# microMouse_schematic.net
KiCad netlist of a schematic drawn in EAGLE
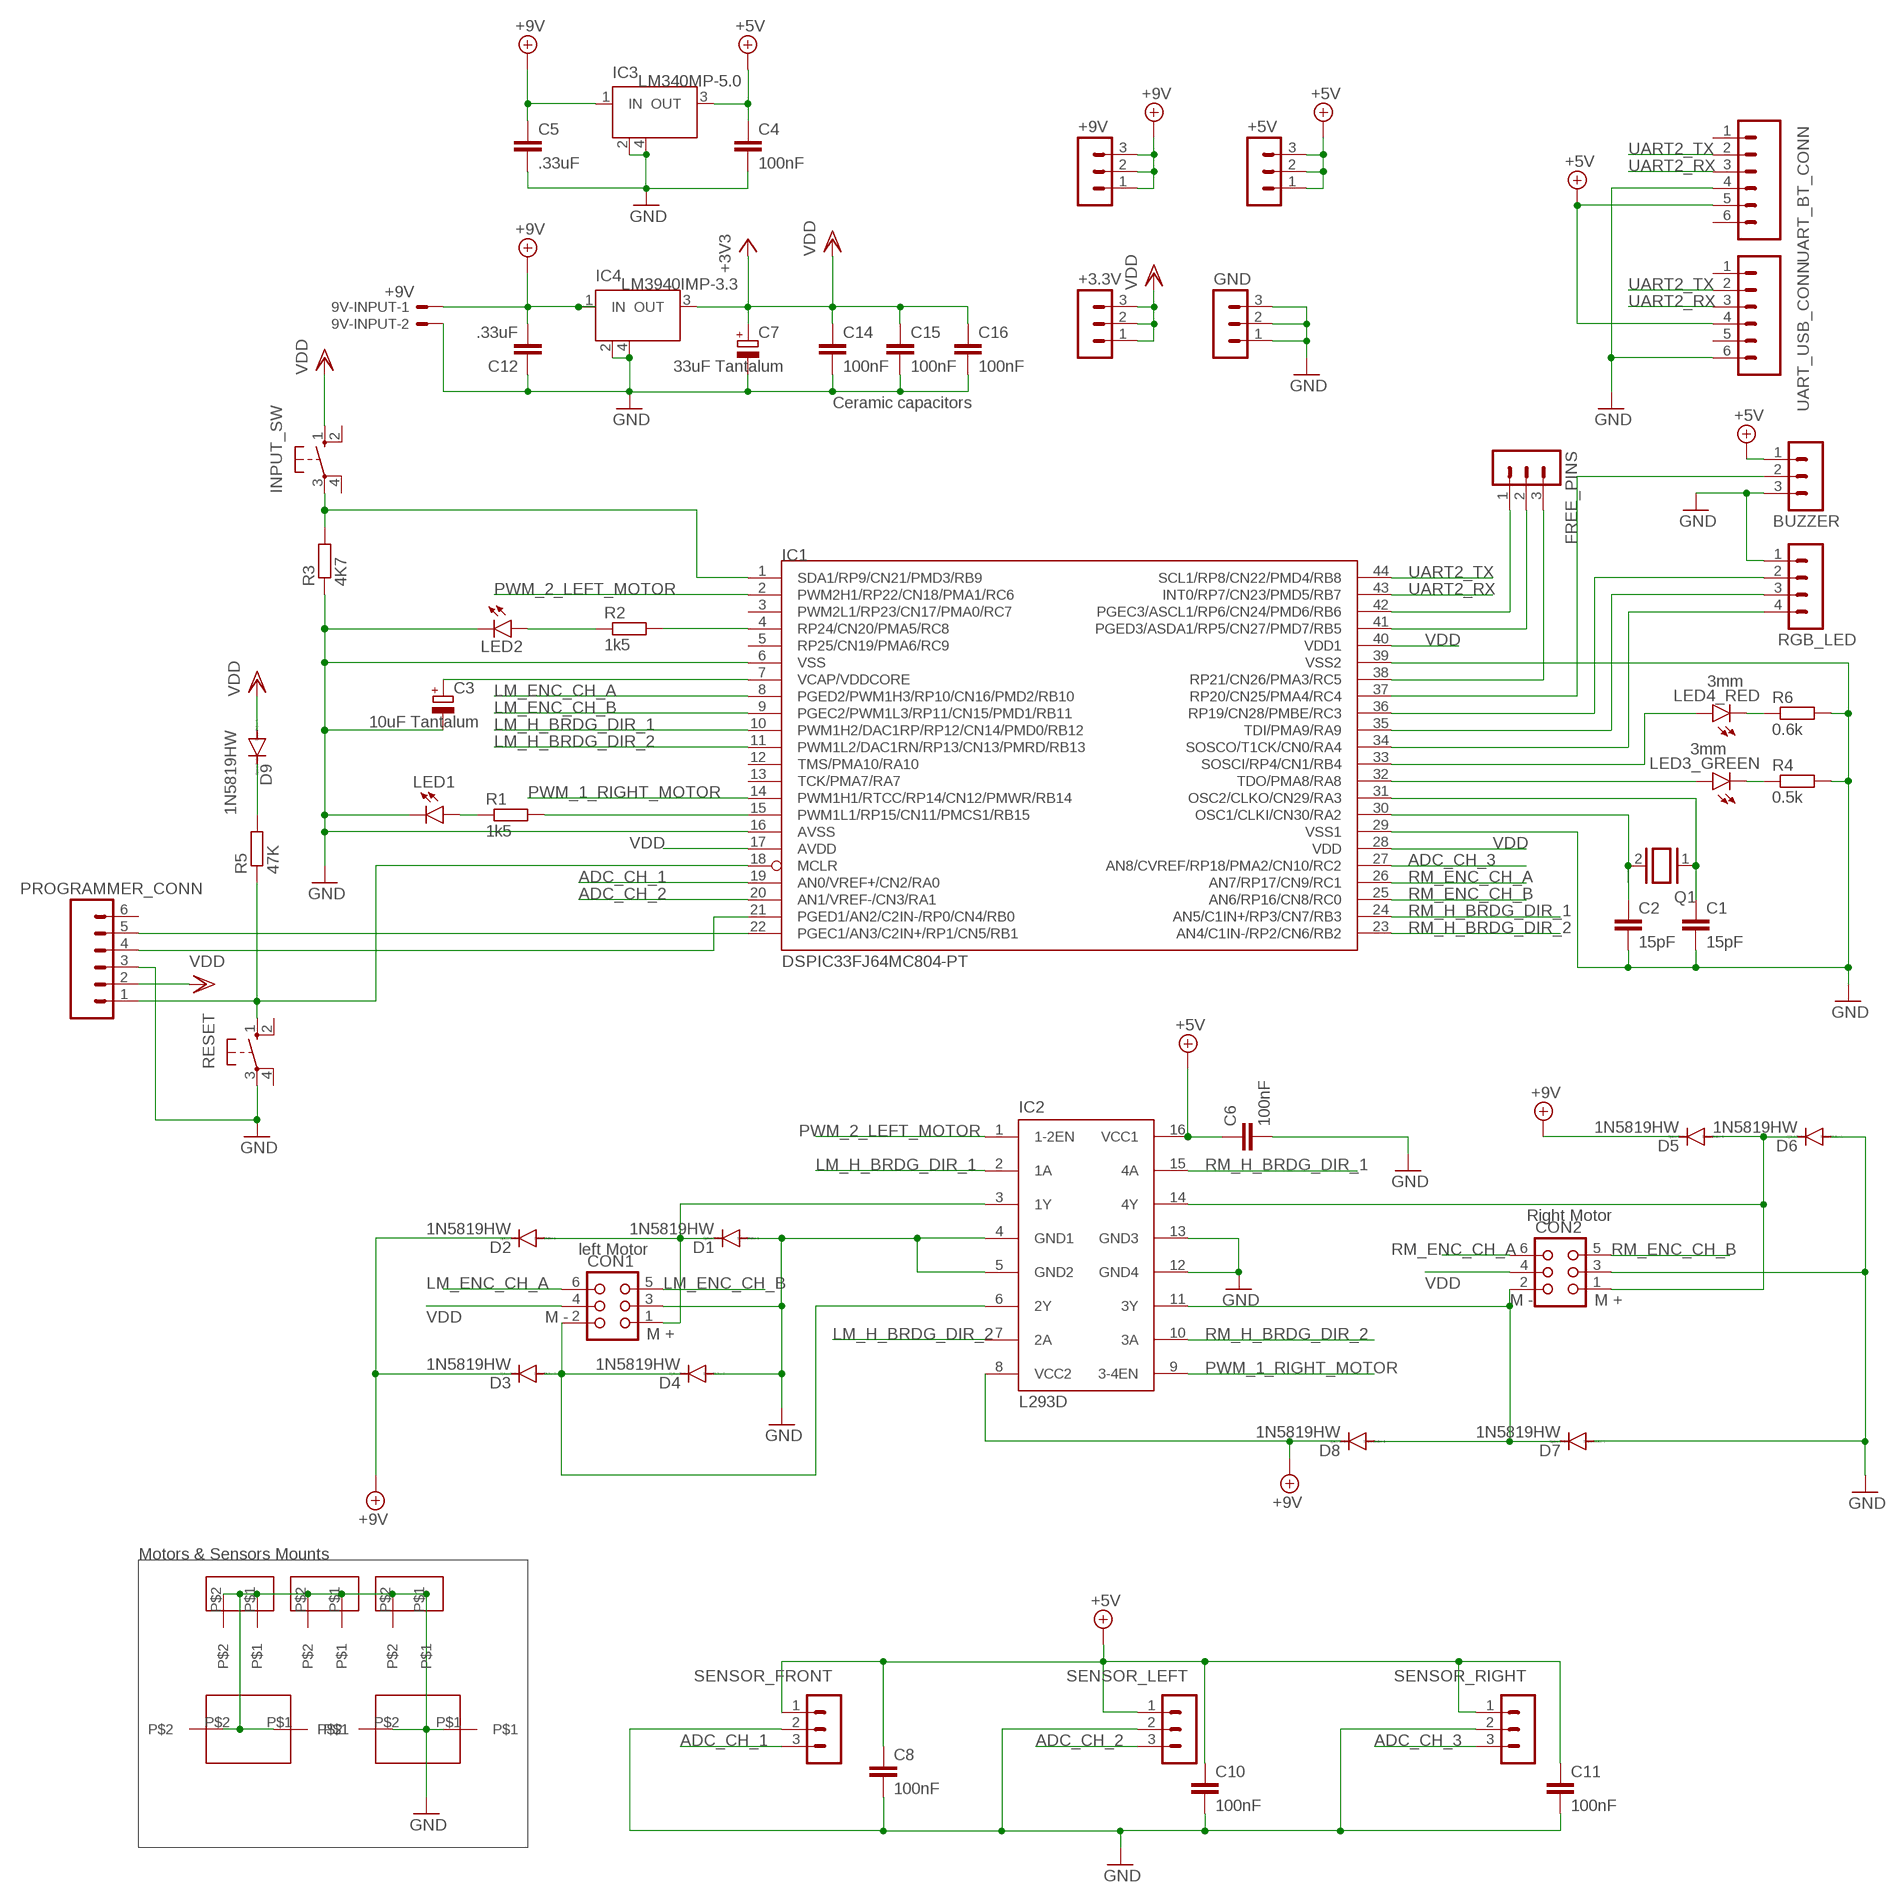
[diagram p0: schematic, sheet 1]

(export (version "E")
  (design (tool "Eeschema 10.0.6"))
  (components
    (comp (ref "+3.3V")
      (value "MA03-1")
      (footprint "eagle-import:MA03-1")
      (libsource (lib "eagle-import") (part "MA03-1"))
    )
    (comp (ref "+5V")
      (value "MA03-1")
      (footprint "eagle-import:MA03-1")
      (libsource (lib "eagle-import") (part "MA03-1"))
    )
    (comp (ref "+9V")
      (value "MA03-1")
      (footprint "eagle-import:MA03-1")
      (libsource (lib "eagle-import") (part "MA03-1"))
    )
    (comp (ref "9V-INPUT")
      (value "+9V")
      (footprint "eagle-import:22-23-2021")
      (fields (field (name "MF") "MOLEX") (field (name "MPN") "22-23-2021"))
      (libsource (lib "eagle-import") (part "22-23-2021"))
    )
    (comp (ref "BUZZER")
      (value "MA03-1")
      (footprint "eagle-import:MA03-1")
      (libsource (lib "eagle-import") (part "MA03-1"))
    )
    (comp (ref "C1")
      (value "15pF")
      (footprint "eagle-import:C0805")
      (libsource (lib "eagle-import") (part "C-EUC0805"))
    )
    (comp (ref "C2")
      (value "15pF")
      (footprint "eagle-import:C0805")
      (libsource (lib "eagle-import") (part "C-EUC0805"))
    )
    (comp (ref "C3")
      (value "10uF Tantalum")
      (footprint "eagle-import:CT3216")
      (libsource (lib "eagle-import") (part "CPOL-EUCT3216"))
    )
    (comp (ref "C4")
      (value "100nF")
      (footprint "eagle-import:C0805")
      (libsource (lib "eagle-import") (part "C-EUC0805"))
    )
    (comp (ref "C5")
      (value ".33uF")
      (footprint "eagle-import:C0805")
      (libsource (lib "eagle-import") (part "C-EUC0805"))
    )
    (comp (ref "C6")
      (value "100nF")
      (footprint "eagle-import:C0805")
      (libsource (lib "eagle-import") (part "C-EUC0805"))
    )
    (comp (ref "C7")
      (value "33uF Tantalum")
      (footprint "eagle-import:CT7343")
      (libsource (lib "eagle-import") (part "CPOL-EUCT7343"))
    )
    (comp (ref "C8")
      (value "100nF")
      (footprint "eagle-import:C0805")
      (libsource (lib "eagle-import") (part "C-EUC0805"))
    )
    (comp (ref "C10")
      (value "100nF")
      (footprint "eagle-import:C0805")
      (libsource (lib "eagle-import") (part "C-EUC0805"))
    )
    (comp (ref "C11")
      (value "100nF")
      (footprint "eagle-import:C0805")
      (libsource (lib "eagle-import") (part "C-EUC0805"))
    )
    (comp (ref "C12")
      (value ".33uF")
      (footprint "eagle-import:C0805")
      (libsource (lib "eagle-import") (part "C-EUC0805"))
    )
    (comp (ref "C14")
      (value "100nF")
      (footprint "eagle-import:C0805")
      (libsource (lib "eagle-import") (part "C-EUC0805"))
    )
    (comp (ref "C15")
      (value "100nF")
      (footprint "eagle-import:C0805")
      (libsource (lib "eagle-import") (part "C-EUC0805"))
    )
    (comp (ref "C16")
      (value "100nF")
      (footprint "eagle-import:C0805")
      (libsource (lib "eagle-import") (part "C-EUC0805"))
    )
    (comp (ref "CON1")
      (value "CON06L")
      (footprint "eagle-import:CON06L")
      (libsource (lib "eagle-import") (part "CON06L"))
    )
    (comp (ref "CON2")
      (value "CON06L")
      (footprint "eagle-import:CON06L")
      (libsource (lib "eagle-import") (part "CON06L"))
    )
    (comp (ref "D1")
      (value "1N5819HW")
      (footprint "eagle-import:SOD-123_MINI-SMA")
      (libsource (lib "eagle-import") (part "CGRM400-G1"))
    )
    (comp (ref "D2")
      (value "1N5819HW")
      (footprint "eagle-import:SOD-123_MINI-SMA")
      (libsource (lib "eagle-import") (part "CGRM400-G1"))
    )
    (comp (ref "D3")
      (value "1N5819HW")
      (footprint "eagle-import:SOD-123_MINI-SMA")
      (libsource (lib "eagle-import") (part "CGRM400-G1"))
    )
    (comp (ref "D4")
      (value "1N5819HW")
      (footprint "eagle-import:SOD-123_MINI-SMA")
      (libsource (lib "eagle-import") (part "CGRM400-G1"))
    )
    (comp (ref "D5")
      (value "1N5819HW")
      (footprint "eagle-import:SOD-123_MINI-SMA")
      (libsource (lib "eagle-import") (part "CGRM400-G1"))
    )
    (comp (ref "D6")
      (value "1N5819HW")
      (footprint "eagle-import:SOD-123_MINI-SMA")
      (libsource (lib "eagle-import") (part "CGRM400-G1"))
    )
    (comp (ref "D7")
      (value "1N5819HW")
      (footprint "eagle-import:SOD-123_MINI-SMA")
      (libsource (lib "eagle-import") (part "CGRM400-G1"))
    )
    (comp (ref "D8")
      (value "1N5819HW")
      (footprint "eagle-import:SOD-123_MINI-SMA")
      (libsource (lib "eagle-import") (part "CGRM400-G1"))
    )
    (comp (ref "D9")
      (value "1N5819HW")
      (footprint "eagle-import:SOD-123_MINI-SMA")
      (libsource (lib "eagle-import") (part "CGRM400-G1"))
    )
    (comp (ref "FREE_PINS")
      (value "MA03-1")
      (footprint "eagle-import:MA03-1")
      (libsource (lib "eagle-import") (part "MA03-1"))
    )
    (comp (ref "GND")
      (value "MA03-1")
      (footprint "eagle-import:MA03-1")
      (libsource (lib "eagle-import") (part "MA03-1"))
    )
    (comp (ref "IC1")
      (value "DSPIC33FJ64MC804-PT")
      (footprint "eagle-import:TQFP44")
      (libsource (lib "eagle-import") (part "DSPIC33FJ64MC804-PT"))
    )
    (comp (ref "IC2")
      (value "L293D")
      (footprint "eagle-import:DIL16")
      (libsource (lib "eagle-import") (part "L293D"))
    )
    (comp (ref "IC3")
      (value "LM340MP-5.0")
      (footprint "eagle-import:SOT223")
      (libsource (lib "eagle-import") (part "LM340S"))
    )
    (comp (ref "IC4")
      (value "LM3940IMP-3.3")
      (footprint "eagle-import:SOT223")
      (libsource (lib "eagle-import") (part "LM340S"))
    )
    (comp (ref "INPUT_SW")
      (value "10-XX")
      (footprint "eagle-import:B3F-10XX")
      (fields (field (name "MPN") "B3F-1000"))
      (libsource (lib "eagle-import") (part "10-XX"))
    )
    (comp (ref "LED1")
      (value "LED5MM")
      (footprint "eagle-import:LED5MM")
      (libsource (lib "eagle-import") (part "LED5MM"))
    )
    (comp (ref "LED2")
      (value "LED5MM")
      (footprint "eagle-import:LED5MM")
      (libsource (lib "eagle-import") (part "LED5MM"))
    )
    (comp (ref "LED3_GREEN")
      (value "3mm")
      (footprint "eagle-import:Q62902-B155")
      (libsource (lib "eagle-import") (part "LEDB155"))
    )
    (comp (ref "LED4_RED")
      (value "3mm")
      (footprint "eagle-import:Q62902-B155")
      (libsource (lib "eagle-import") (part "LEDB155"))
    )
    (comp (ref "PROGRAMMER_CONN")
      (value "M06")
      (footprint "eagle-import:06P")
      (libsource (lib "eagle-import") (part "M06"))
    )
    (comp (ref "Q1")
      (value "XTAL/S")
      (footprint "eagle-import:QS")
      (libsource (lib "eagle-import") (part "XTAL/S"))
    )
    (comp (ref "R1")
      (value "1k5")
      (footprint "eagle-import:R0805")
      (libsource (lib "eagle-import") (part "R-EU_R0805"))
    )
    (comp (ref "R2")
      (value "1k5")
      (footprint "eagle-import:R0805")
      (libsource (lib "eagle-import") (part "R-EU_R0805"))
    )
    (comp (ref "R3")
      (value "4K7")
      (footprint "eagle-import:R0805")
      (libsource (lib "eagle-import") (part "R-EU_R0805"))
    )
    (comp (ref "R4")
      (value "0.5k")
      (footprint "eagle-import:R0805")
      (libsource (lib "eagle-import") (part "R-EU_R0805"))
    )
    (comp (ref "R5")
      (value "47K")
      (footprint "eagle-import:R0805")
      (libsource (lib "eagle-import") (part "R-EU_R0805"))
    )
    (comp (ref "R6")
      (value "0.6k")
      (footprint "eagle-import:R0805")
      (libsource (lib "eagle-import") (part "R-EU_R0805"))
    )
    (comp (ref "RESET")
      (value "10-XX")
      (footprint "eagle-import:B3F-10XX")
      (fields (field (name "MPN") "B3F-1000"))
      (libsource (lib "eagle-import") (part "10-XX"))
    )
    (comp (ref "RGB_LED")
      (value "MA04-1")
      (footprint "eagle-import:MA04-1")
      (libsource (lib "eagle-import") (part "MA04-1"))
    )
    (comp (ref "SENSOR_FRONT")
      (value "MA03-1")
      (footprint "eagle-import:MA03-1")
      (libsource (lib "eagle-import") (part "MA03-1"))
    )
    (comp (ref "SENSOR_LEFT")
      (value "MA03-1")
      (footprint "eagle-import:MA03-1")
      (libsource (lib "eagle-import") (part "MA03-1"))
    )
    (comp (ref "SENSOR_RIGHT")
      (value "MA03-1")
      (footprint "eagle-import:MA03-1")
      (libsource (lib "eagle-import") (part "MA03-1"))
    )
    (comp (ref "SENS_MNT_F")
      (value "SENSOR_MOUNT_F")
      (footprint "eagle-import:SENSOR_MOUNT")
      (libsource (lib "eagle-import") (part "SENSOR_MOUNT"))
    )
    (comp (ref "SENS_MNT_L")
      (value "SENSOR_MOUNT_L")
      (footprint "eagle-import:SENSOR_MOUNT")
      (libsource (lib "eagle-import") (part "SENSOR_MOUNT"))
    )
    (comp (ref "SENS_MNT_R")
      (value "SENSOR_MOUNT_R")
      (footprint "eagle-import:SENSOR_MOUNT")
      (libsource (lib "eagle-import") (part "SENSOR_MOUNT"))
    )
    (comp (ref "U$1")
      (value "MOTOR_MOUNT")
      (footprint "eagle-import:MOTOR_MOUNT")
      (libsource (lib "eagle-import") (part "MOTOR_MOUNT"))
    )
    (comp (ref "U$2")
      (value "MOTOR_MOUNT")
      (footprint "eagle-import:MOTOR_MOUNT")
      (libsource (lib "eagle-import") (part "MOTOR_MOUNT"))
    )
    (comp (ref "UART_BT_CONN")
      (value "M06")
      (footprint "eagle-import:06P")
      (libsource (lib "eagle-import") (part "M06"))
    )
    (comp (ref "UART_USB_CONN")
      (value "M06")
      (footprint "eagle-import:06P")
      (libsource (lib "eagle-import") (part "M06"))
    )
  )
  (nets
    (net (code "1") (name "+3V3") (class "Default")
      (node (ref "+3.3V") (pin "1") (pinfunction "1_1") (pintype "passive"))
      (node (ref "+3.3V") (pin "2") (pinfunction "2_2") (pintype "passive"))
      (node (ref "+3.3V") (pin "3") (pinfunction "3_3") (pintype "passive"))
      (node (ref "C14") (pin "1") (pinfunction "1_1") (pintype "passive"))
      (node (ref "C15") (pin "1") (pinfunction "1_1") (pintype "passive"))
      (node (ref "C16") (pin "1") (pinfunction "1_1") (pintype "passive"))
      (node (ref "C7") (pin "+") (pinfunction "+_+") (pintype "passive"))
      (node (ref "CON1") (pin "4") (pinfunction "4_4") (pintype "passive"))
      (node (ref "CON2") (pin "4") (pinfunction "4_4") (pintype "passive"))
      (node (ref "D9") (pin "A") (pinfunction "A_A") (pintype "passive"))
      (node (ref "IC1") (pin "17") (pinfunction "AVDD_17") (pintype "power_in"))
      (node (ref "IC1") (pin "28") (pinfunction "VDD_28") (pintype "power_in"))
      (node (ref "IC1") (pin "40") (pinfunction "VDD1_40") (pintype "power_in"))
      (node (ref "IC4") (pin "3") (pinfunction "OUT_3") (pintype "passive"))
      (node (ref "INPUT_SW") (pin "1") (pinfunction "S_1") (pintype "passive"))
      (node (ref "PROGRAMMER_CONN") (pin "2") (pinfunction "2_2") (pintype "passive"))
    )
    (net (code "2") (name "+5V") (class "Default")
      (node (ref "+5V") (pin "1") (pinfunction "1_1") (pintype "passive"))
      (node (ref "+5V") (pin "2") (pinfunction "2_2") (pintype "passive"))
      (node (ref "+5V") (pin "3") (pinfunction "3_3") (pintype "passive"))
      (node (ref "BUZZER") (pin "1") (pinfunction "1_1") (pintype "passive"))
      (node (ref "C10") (pin "1") (pinfunction "1_1") (pintype "passive"))
      (node (ref "C11") (pin "1") (pinfunction "1_1") (pintype "passive"))
      (node (ref "C4") (pin "1") (pinfunction "1_1") (pintype "passive"))
      (node (ref "C6") (pin "1") (pinfunction "1_1") (pintype "passive"))
      (node (ref "C8") (pin "1") (pinfunction "1_1") (pintype "passive"))
      (node (ref "IC2") (pin "16") (pinfunction "VCC1_16") (pintype "power_in"))
      (node (ref "IC3") (pin "3") (pinfunction "OUT_3") (pintype "passive"))
      (node (ref "SENSOR_FRONT") (pin "1") (pinfunction "1_1") (pintype "passive"))
      (node (ref "SENSOR_LEFT") (pin "1") (pinfunction "1_1") (pintype "passive"))
      (node (ref "SENSOR_RIGHT") (pin "1") (pinfunction "1_1") (pintype "passive"))
      (node (ref "UART_BT_CONN") (pin "5") (pinfunction "5_5") (pintype "passive"))
      (node (ref "UART_USB_CONN") (pin "4") (pinfunction "4_4") (pintype "passive"))
    )
    (net (code "3") (name "+9V") (class "Default")
      (node (ref "+9V") (pin "1") (pinfunction "1_1") (pintype "passive"))
      (node (ref "+9V") (pin "2") (pinfunction "2_2") (pintype "passive"))
      (node (ref "+9V") (pin "3") (pinfunction "3_3") (pintype "passive"))
      (node (ref "9V-INPUT") (pin "1") (pinfunction "S_1") (pintype "passive"))
      (node (ref "C12") (pin "2") (pinfunction "2_2") (pintype "passive"))
      (node (ref "C5") (pin "1") (pinfunction "1_1") (pintype "passive"))
      (node (ref "D2") (pin "C") (pinfunction "C_C") (pintype "passive"))
      (node (ref "D3") (pin "C") (pinfunction "C_C") (pintype "passive"))
      (node (ref "D5") (pin "C") (pinfunction "C_C") (pintype "passive"))
      (node (ref "D8") (pin "C") (pinfunction "C_C") (pintype "passive"))
      (node (ref "IC2") (pin "8") (pinfunction "VCC2_8") (pintype "power_in"))
      (node (ref "IC3") (pin "1") (pinfunction "IN_1") (pintype "input"))
      (node (ref "IC4") (pin "1") (pinfunction "IN_1") (pintype "input"))
    )
    (net (code "4") (name "/ADC_CH_1") (class "Default")
      (node (ref "IC1") (pin "19") (pinfunction "AN0/VREF+/CN2/RA0_19") (pintype "bidirectional"))
      (node (ref "SENSOR_FRONT") (pin "3") (pinfunction "3_3") (pintype "passive"))
    )
    (net (code "5") (name "/ADC_CH_2") (class "Default")
      (node (ref "IC1") (pin "20") (pinfunction "AN1/VREF-/CN3/RA1_20") (pintype "bidirectional"))
      (node (ref "SENSOR_LEFT") (pin "3") (pinfunction "3_3") (pintype "passive"))
    )
    (net (code "6") (name "/ADC_CH_3") (class "Default")
      (node (ref "IC1") (pin "27") (pinfunction "AN8/CVREF/RP18/PMA2/CN10/RC2_27") (pintype "bidirectional"))
      (node (ref "SENSOR_RIGHT") (pin "3") (pinfunction "3_3") (pintype "passive"))
    )
    (net (code "7") (name "/LM_ENC_CH_A") (class "Default")
      (node (ref "CON1") (pin "6") (pinfunction "6_6") (pintype "passive"))
      (node (ref "IC1") (pin "8") (pinfunction "PGED2/PWM1H3/RP10/CN16/PMD2/RB10_8") (pintype "bidirectional"))
    )
    (net (code "8") (name "/LM_ENC_CH_B") (class "Default")
      (node (ref "CON1") (pin "5") (pinfunction "5_5") (pintype "passive"))
      (node (ref "IC1") (pin "9") (pinfunction "PGEC2/PWM1L3/RP11/CN15/PMD1/RB11_9") (pintype "bidirectional"))
    )
    (net (code "9") (name "/LM_H_BRDG_DIR_1") (class "Default")
      (node (ref "IC1") (pin "10") (pinfunction "PWM1H2/DAC1RP/RP12/CN14/PMD0/RB12_10") (pintype "bidirectional"))
      (node (ref "IC2") (pin "2") (pinfunction "1A_2") (pintype "input"))
    )
    (net (code "10") (name "/LM_H_BRDG_DIR_2") (class "Default")
      (node (ref "IC1") (pin "11") (pinfunction "PWM1L2/DAC1RN/RP13/CN13/PMRD/RB13_11") (pintype "bidirectional"))
      (node (ref "IC2") (pin "7") (pinfunction "2A_7") (pintype "input"))
    )
    (net (code "11") (name "/PWM_1_RIGHT_MOTOR") (class "Default")
      (node (ref "IC1") (pin "14") (pinfunction "PWM1H1/RTCC/RP14/CN12/PMWR/RB14_14") (pintype "bidirectional"))
      (node (ref "IC2") (pin "9") (pinfunction "3-4EN_9") (pintype "input"))
    )
    (net (code "12") (name "/PWM_2_LEFT_MOTOR") (class "Default")
      (node (ref "IC1") (pin "2") (pinfunction "PWM2H1/RP22/CN18/PMA1/RC6_2") (pintype "bidirectional"))
      (node (ref "IC2") (pin "1") (pinfunction "1-2EN_1") (pintype "input"))
    )
    (net (code "13") (name "/RM_ENC_CH_A") (class "Default")
      (node (ref "CON2") (pin "6") (pinfunction "6_6") (pintype "passive"))
      (node (ref "IC1") (pin "26") (pinfunction "AN7/RP17/CN9/RC1_26") (pintype "bidirectional"))
    )
    (net (code "14") (name "/RM_ENC_CH_B") (class "Default")
      (node (ref "CON2") (pin "5") (pinfunction "5_5") (pintype "passive"))
      (node (ref "IC1") (pin "25") (pinfunction "AN6/RP16/CN8/RC0_25") (pintype "bidirectional"))
    )
    (net (code "15") (name "/RM_H_BRDG_DIR_1") (class "Default")
      (node (ref "IC1") (pin "24") (pinfunction "AN5/C1IN+/RP3/CN7/RB3_24") (pintype "bidirectional"))
      (node (ref "IC2") (pin "15") (pinfunction "4A_15") (pintype "input"))
    )
    (net (code "16") (name "/RM_H_BRDG_DIR_2") (class "Default")
      (node (ref "IC1") (pin "23") (pinfunction "AN4/C1IN-/RP2/CN6/RB2_23") (pintype "bidirectional"))
      (node (ref "IC2") (pin "10") (pinfunction "3A_10") (pintype "input"))
    )
    (net (code "17") (name "/UART2_RX") (class "Default")
      (node (ref "IC1") (pin "43") (pinfunction "INT0/RP7/CN23/PMD5/RB7_43") (pintype "bidirectional"))
      (node (ref "UART_BT_CONN") (pin "3") (pinfunction "3_3") (pintype "passive"))
      (node (ref "UART_USB_CONN") (pin "3") (pinfunction "3_3") (pintype "passive"))
    )
    (net (code "18") (name "/UART2_TX") (class "Default")
      (node (ref "IC1") (pin "44") (pinfunction "SCL1/RP8/CN22/PMD4/RB8_44") (pintype "bidirectional"))
      (node (ref "UART_BT_CONN") (pin "2") (pinfunction "2_2") (pintype "passive"))
      (node (ref "UART_USB_CONN") (pin "2") (pinfunction "2_2") (pintype "passive"))
    )
    (net (code "19") (name "GND") (class "Default")
      (node (ref "9V-INPUT") (pin "2") (pinfunction "S_2") (pintype "passive"))
      (node (ref "BUZZER") (pin "3") (pinfunction "3_3") (pintype "passive"))
      (node (ref "C1") (pin "2") (pinfunction "2_2") (pintype "passive"))
      (node (ref "C10") (pin "2") (pinfunction "2_2") (pintype "passive"))
      (node (ref "C11") (pin "2") (pinfunction "2_2") (pintype "passive"))
      (node (ref "C12") (pin "1") (pinfunction "1_1") (pintype "passive"))
      (node (ref "C14") (pin "2") (pinfunction "2_2") (pintype "passive"))
      (node (ref "C15") (pin "2") (pinfunction "2_2") (pintype "passive"))
      (node (ref "C16") (pin "2") (pinfunction "2_2") (pintype "passive"))
      (node (ref "C2") (pin "2") (pinfunction "2_2") (pintype "passive"))
      (node (ref "C3") (pin "-") (pinfunction "-_-") (pintype "passive"))
      (node (ref "C4") (pin "2") (pinfunction "2_2") (pintype "passive"))
      (node (ref "C5") (pin "2") (pinfunction "2_2") (pintype "passive"))
      (node (ref "C6") (pin "2") (pinfunction "2_2") (pintype "passive"))
      (node (ref "C7") (pin "-") (pinfunction "-_-") (pintype "passive"))
      (node (ref "C8") (pin "2") (pinfunction "2_2") (pintype "passive"))
      (node (ref "CON1") (pin "3") (pinfunction "3_3") (pintype "passive"))
      (node (ref "CON2") (pin "3") (pinfunction "3_3") (pintype "passive"))
      (node (ref "D1") (pin "A") (pinfunction "A_A") (pintype "passive"))
      (node (ref "D4") (pin "A") (pinfunction "A_A") (pintype "passive"))
      (node (ref "D6") (pin "A") (pinfunction "A_A") (pintype "passive"))
      (node (ref "D7") (pin "A") (pinfunction "A_A") (pintype "passive"))
      (node (ref "GND") (pin "1") (pinfunction "1_1") (pintype "passive"))
      (node (ref "GND") (pin "2") (pinfunction "2_2") (pintype "passive"))
      (node (ref "GND") (pin "3") (pinfunction "3_3") (pintype "passive"))
      (node (ref "IC1") (pin "16") (pinfunction "AVSS_16") (pintype "power_in"))
      (node (ref "IC1") (pin "29") (pinfunction "VSS1_29") (pintype "power_in"))
      (node (ref "IC1") (pin "39") (pinfunction "VSS2_39") (pintype "power_in"))
      (node (ref "IC1") (pin "6") (pinfunction "VSS_6") (pintype "power_in"))
      (node (ref "IC2") (pin "12") (pinfunction "GND4_12") (pintype "power_in"))
      (node (ref "IC2") (pin "13") (pinfunction "GND3_13") (pintype "power_in"))
      (node (ref "IC2") (pin "4") (pinfunction "GND1_4") (pintype "power_in"))
      (node (ref "IC2") (pin "5") (pinfunction "GND2_5") (pintype "power_in"))
      (node (ref "IC3") (pin "2") (pinfunction "GND_2") (pintype "power_in"))
      (node (ref "IC3") (pin "4") (pinfunction "GND_4") (pintype "power_in"))
      (node (ref "IC4") (pin "2") (pinfunction "GND_2") (pintype "power_in"))
      (node (ref "IC4") (pin "4") (pinfunction "GND_4") (pintype "power_in"))
      (node (ref "LED1") (pin "K") (pinfunction "C_K") (pintype "passive"))
      (node (ref "LED2") (pin "K") (pinfunction "C_K") (pintype "passive"))
      (node (ref "PROGRAMMER_CONN") (pin "3") (pinfunction "3_3") (pintype "passive"))
      (node (ref "R3") (pin "1") (pinfunction "1_1") (pintype "passive"))
      (node (ref "R4") (pin "2") (pinfunction "2_2") (pintype "passive"))
      (node (ref "R6") (pin "2") (pinfunction "2_2") (pintype "passive"))
      (node (ref "RESET") (pin "3") (pinfunction "P_3") (pintype "passive"))
      (node (ref "RGB_LED") (pin "1") (pinfunction "1_1") (pintype "passive"))
      (node (ref "SENSOR_FRONT") (pin "2") (pinfunction "2_2") (pintype "passive"))
      (node (ref "SENSOR_LEFT") (pin "2") (pinfunction "2_2") (pintype "passive"))
      (node (ref "SENSOR_RIGHT") (pin "2") (pinfunction "2_2") (pintype "passive"))
      (node (ref "SENS_MNT_F") (pin "P$1") (pinfunction "P$1_P$1") (pintype "bidirectional"))
      (node (ref "SENS_MNT_F") (pin "P$2") (pinfunction "P$2_P$2") (pintype "bidirectional"))
      (node (ref "SENS_MNT_L") (pin "P$1") (pinfunction "P$1_P$1") (pintype "bidirectional"))
      (node (ref "SENS_MNT_L") (pin "P$2") (pinfunction "P$2_P$2") (pintype "bidirectional"))
      (node (ref "SENS_MNT_R") (pin "P$1") (pinfunction "P$1_P$1") (pintype "bidirectional"))
      (node (ref "SENS_MNT_R") (pin "P$2") (pinfunction "P$2_P$2") (pintype "bidirectional"))
      (node (ref "U$1") (pin "P$1") (pinfunction "P$1_P$1") (pintype "bidirectional"))
      (node (ref "U$1") (pin "P$2") (pinfunction "P$2_P$2") (pintype "bidirectional"))
      (node (ref "U$2") (pin "P$1") (pinfunction "P$1_P$1") (pintype "bidirectional"))
      (node (ref "U$2") (pin "P$2") (pinfunction "P$2_P$2") (pintype "bidirectional"))
      (node (ref "UART_BT_CONN") (pin "4") (pinfunction "4_4") (pintype "passive"))
      (node (ref "UART_USB_CONN") (pin "6") (pinfunction "6_6") (pintype "passive"))
    )
    (net (code "20") (name "Net-(D9-PadC)") (class "Default")
      (node (ref "D9") (pin "C") (pinfunction "C_C") (pintype "passive"))
      (node (ref "R5") (pin "2") (pinfunction "2_2") (pintype "passive"))
    )
    (net (code "21") (name "Net-(IC1-MCLR)") (class "Default")
      (node (ref "IC1") (pin "18") (pinfunction "MCLR_18") (pintype "input"))
      (node (ref "PROGRAMMER_CONN") (pin "1") (pinfunction "1_1") (pintype "passive"))
      (node (ref "R5") (pin "1") (pinfunction "1_1") (pintype "passive"))
      (node (ref "RESET") (pin "1") (pinfunction "S_1") (pintype "passive"))
    )
    (net (code "22") (name "Net-(IC1-OSC1{slash}CLKI{slash}CN30{slash}RA2)") (class "Default")
      (node (ref "C2") (pin "1") (pinfunction "1_1") (pintype "passive"))
      (node (ref "IC1") (pin "30") (pinfunction "OSC1/CLKI/CN30/RA2_30") (pintype "bidirectional"))
      (node (ref "Q1") (pin "2") (pinfunction "2_2") (pintype "passive"))
    )
    (net (code "23") (name "Net-(IC1-OSC2{slash}CLKO{slash}CN29{slash}RA3)") (class "Default")
      (node (ref "C1") (pin "1") (pinfunction "1_1") (pintype "passive"))
      (node (ref "IC1") (pin "31") (pinfunction "OSC2/CLKO/CN29/RA3_31") (pintype "bidirectional"))
      (node (ref "Q1") (pin "1") (pinfunction "1_1") (pintype "passive"))
    )
    (net (code "24") (name "Net-(IC1-PGEC1{slash}AN3{slash}C2IN+{slash}RP1{slash}CN5{slash}RB1)") (class "Default")
      (node (ref "IC1") (pin "22") (pinfunction "PGEC1/AN3/C2IN+/RP1/CN5/RB1_22") (pintype "bidirectional"))
      (node (ref "PROGRAMMER_CONN") (pin "5") (pinfunction "5_5") (pintype "passive"))
    )
    (net (code "25") (name "Net-(IC1-PGEC3{slash}ASCL1{slash}RP6{slash}CN24{slash}PMD6{slash}RB6)") (class "Default")
      (node (ref "FREE_PINS") (pin "1") (pinfunction "1_1") (pintype "passive"))
      (node (ref "IC1") (pin "42") (pinfunction "PGEC3/ASCL1/RP6/CN24/PMD6/RB6_42") (pintype "bidirectional"))
    )
    (net (code "26") (name "Net-(IC1-PGED1{slash}AN2{slash}C2IN-{slash}RP0{slash}CN4{slash}RB0)") (class "Default")
      (node (ref "IC1") (pin "21") (pinfunction "PGED1/AN2/C2IN-/RP0/CN4/RB0_21") (pintype "bidirectional"))
      (node (ref "PROGRAMMER_CONN") (pin "4") (pinfunction "4_4") (pintype "passive"))
    )
    (net (code "27") (name "Net-(IC1-PGED3{slash}ASDA1{slash}RP5{slash}CN27{slash}PMD7{slash}RB5)") (class "Default")
      (node (ref "FREE_PINS") (pin "2") (pinfunction "2_2") (pintype "passive"))
      (node (ref "IC1") (pin "41") (pinfunction "PGED3/ASDA1/RP5/CN27/PMD7/RB5_41") (pintype "bidirectional"))
    )
    (net (code "28") (name "Net-(IC1-PWM1L1{slash}RP15{slash}CN11{slash}PMCS1{slash}RB15)") (class "Default")
      (node (ref "IC1") (pin "15") (pinfunction "PWM1L1/RP15/CN11/PMCS1/RB15_15") (pintype "bidirectional"))
      (node (ref "R1") (pin "2") (pinfunction "2_2") (pintype "passive"))
    )
    (net (code "29") (name "Net-(IC1-RP19{slash}CN28{slash}PMBE{slash}RC3)") (class "Default")
      (node (ref "IC1") (pin "36") (pinfunction "RP19/CN28/PMBE/RC3_36") (pintype "bidirectional"))
      (node (ref "RGB_LED") (pin "2") (pinfunction "2_2") (pintype "passive"))
    )
    (net (code "30") (name "Net-(IC1-RP20{slash}CN25{slash}PMA4{slash}RC4)") (class "Default")
      (node (ref "BUZZER") (pin "2") (pinfunction "2_2") (pintype "passive"))
      (node (ref "IC1") (pin "37") (pinfunction "RP20/CN25/PMA4/RC4_37") (pintype "bidirectional"))
    )
    (net (code "31") (name "Net-(IC1-RP21{slash}CN26{slash}PMA3{slash}RC5)") (class "Default")
      (node (ref "FREE_PINS") (pin "3") (pinfunction "3_3") (pintype "passive"))
      (node (ref "IC1") (pin "38") (pinfunction "RP21/CN26/PMA3/RC5_38") (pintype "bidirectional"))
    )
    (net (code "32") (name "Net-(IC1-RP24{slash}CN20{slash}PMA5{slash}RC8)") (class "Default")
      (node (ref "IC1") (pin "4") (pinfunction "RP24/CN20/PMA5/RC8_4") (pintype "bidirectional"))
      (node (ref "R2") (pin "2") (pinfunction "2_2") (pintype "passive"))
    )
    (net (code "33") (name "Net-(IC1-SDA1{slash}RP9{slash}CN21{slash}PMD3{slash}RB9)") (class "Default")
      (node (ref "IC1") (pin "1") (pinfunction "SDA1/RP9/CN21/PMD3/RB9_1") (pintype "bidirectional"))
      (node (ref "INPUT_SW") (pin "3") (pinfunction "P_3") (pintype "passive"))
      (node (ref "R3") (pin "2") (pinfunction "2_2") (pintype "passive"))
    )
    (net (code "34") (name "Net-(IC1-SOSCI{slash}RP4{slash}CN1{slash}RB4)") (class "Default")
      (node (ref "IC1") (pin "33") (pinfunction "SOSCI/RP4/CN1/RB4_33") (pintype "bidirectional"))
      (node (ref "LED4_RED") (pin "A") (pinfunction "A_A") (pintype "passive"))
    )
    (net (code "35") (name "Net-(IC1-SOSCO{slash}T1CK{slash}CN0{slash}RA4)") (class "Default")
      (node (ref "IC1") (pin "34") (pinfunction "SOSCO/T1CK/CN0/RA4_34") (pintype "bidirectional"))
      (node (ref "RGB_LED") (pin "4") (pinfunction "4_4") (pintype "passive"))
    )
    (net (code "36") (name "Net-(IC1-TDI{slash}PMA9{slash}RA9)") (class "Default")
      (node (ref "IC1") (pin "35") (pinfunction "TDI/PMA9/RA9_35") (pintype "bidirectional"))
      (node (ref "RGB_LED") (pin "3") (pinfunction "3_3") (pintype "passive"))
    )
    (net (code "37") (name "Net-(IC1-TDO{slash}PMA8{slash}RA8)") (class "Default")
      (node (ref "IC1") (pin "32") (pinfunction "TDO/PMA8/RA8_32") (pintype "bidirectional"))
      (node (ref "LED3_GREEN") (pin "A") (pinfunction "A_A") (pintype "passive"))
    )
    (net (code "38") (name "Net-(IC1-VCAP{slash}VDDCORE)") (class "Default")
      (node (ref "C3") (pin "+") (pinfunction "+_+") (pintype "passive"))
      (node (ref "IC1") (pin "7") (pinfunction "VCAP/VDDCORE_7") (pintype "power_in"))
    )
    (net (code "39") (name "Net-(IC2-1Y)") (class "Default")
      (node (ref "CON1") (pin "1") (pinfunction "1_1") (pintype "passive"))
      (node (ref "D1") (pin "C") (pinfunction "C_C") (pintype "passive"))
      (node (ref "D2") (pin "A") (pinfunction "A_A") (pintype "passive"))
      (node (ref "IC2") (pin "3") (pinfunction "1Y_3") (pintype "output"))
    )
    (net (code "40") (name "Net-(IC2-2Y)") (class "Default")
      (node (ref "CON1") (pin "2") (pinfunction "2_2") (pintype "passive"))
      (node (ref "D3") (pin "A") (pinfunction "A_A") (pintype "passive"))
      (node (ref "D4") (pin "C") (pinfunction "C_C") (pintype "passive"))
      (node (ref "IC2") (pin "6") (pinfunction "2Y_6") (pintype "output"))
    )
    (net (code "41") (name "Net-(IC2-3Y)") (class "Default")
      (node (ref "CON2") (pin "2") (pinfunction "2_2") (pintype "passive"))
      (node (ref "D7") (pin "C") (pinfunction "C_C") (pintype "passive"))
      (node (ref "D8") (pin "A") (pinfunction "A_A") (pintype "passive"))
      (node (ref "IC2") (pin "11") (pinfunction "3Y_11") (pintype "output"))
    )
    (net (code "42") (name "Net-(IC2-4Y)") (class "Default")
      (node (ref "CON2") (pin "1") (pinfunction "1_1") (pintype "passive"))
      (node (ref "D5") (pin "A") (pinfunction "A_A") (pintype "passive"))
      (node (ref "D6") (pin "C") (pinfunction "C_C") (pintype "passive"))
      (node (ref "IC2") (pin "14") (pinfunction "4Y_14") (pintype "output"))
    )
    (net (code "43") (name "Net-(LED1-PadA)") (class "Default")
      (node (ref "LED1") (pin "A") (pinfunction "A_A") (pintype "passive"))
      (node (ref "R1") (pin "1") (pinfunction "1_1") (pintype "passive"))
    )
    (net (code "44") (name "Net-(LED2-PadA)") (class "Default")
      (node (ref "LED2") (pin "A") (pinfunction "A_A") (pintype "passive"))
      (node (ref "R2") (pin "1") (pinfunction "1_1") (pintype "passive"))
    )
    (net (code "45") (name "Net-(LED3_GREEN-C)") (class "Default")
      (node (ref "LED3_GREEN") (pin "K") (pinfunction "C_K") (pintype "passive"))
      (node (ref "R4") (pin "1") (pinfunction "1_1") (pintype "passive"))
    )
    (net (code "46") (name "Net-(LED4_RED-C)") (class "Default")
      (node (ref "LED4_RED") (pin "K") (pinfunction "C_K") (pintype "passive"))
      (node (ref "R6") (pin "1") (pinfunction "1_1") (pintype "passive"))
    )
    (net (code "47") (name "unconnected-(IC1-PWM2L1{slash}RP23{slash}CN17{slash}PMA0{slash}RC7-Pad3)") (class "Default")
      (node (ref "IC1") (pin "3") (pinfunction "PWM2L1/RP23/CN17/PMA0/RC7_3") (pintype "bidirectional"))
    )
    (net (code "48") (name "unconnected-(IC1-RP25{slash}CN19{slash}PMA6{slash}RC9-Pad5)") (class "Default")
      (node (ref "IC1") (pin "5") (pinfunction "RP25/CN19/PMA6/RC9_5") (pintype "bidirectional"))
    )
    (net (code "49") (name "unconnected-(IC1-TCK{slash}PMA7{slash}RA7-Pad13)") (class "Default")
      (node (ref "IC1") (pin "13") (pinfunction "TCK/PMA7/RA7_13") (pintype "bidirectional"))
    )
    (net (code "50") (name "unconnected-(IC1-TMS{slash}PMA10{slash}RA10-Pad12)") (class "Default")
      (node (ref "IC1") (pin "12") (pinfunction "TMS/PMA10/RA10_12") (pintype "bidirectional"))
    )
    (net (code "51") (name "unconnected-(INPUT_SW-P1-Pad4)") (class "Default")
      (node (ref "INPUT_SW") (pin "4") (pinfunction "P1_4") (pintype "passive"))
    )
    (net (code "52") (name "unconnected-(INPUT_SW-S1-Pad2)") (class "Default")
      (node (ref "INPUT_SW") (pin "2") (pinfunction "S1_2") (pintype "passive"))
    )
    (net (code "53") (name "unconnected-(PROGRAMMER_CONN-Pad6)") (class "Default")
      (node (ref "PROGRAMMER_CONN") (pin "6") (pinfunction "6_6") (pintype "passive"))
    )
    (net (code "54") (name "unconnected-(RESET-P1-Pad4)") (class "Default")
      (node (ref "RESET") (pin "4") (pinfunction "P1_4") (pintype "passive"))
    )
    (net (code "55") (name "unconnected-(RESET-S1-Pad2)") (class "Default")
      (node (ref "RESET") (pin "2") (pinfunction "S1_2") (pintype "passive"))
    )
    (net (code "56") (name "unconnected-(UART_BT_CONN-Pad1)") (class "Default")
      (node (ref "UART_BT_CONN") (pin "1") (pinfunction "1_1") (pintype "passive"))
    )
    (net (code "57") (name "unconnected-(UART_BT_CONN-Pad6)") (class "Default")
      (node (ref "UART_BT_CONN") (pin "6") (pinfunction "6_6") (pintype "passive"))
    )
    (net (code "58") (name "unconnected-(UART_USB_CONN-Pad1)") (class "Default")
      (node (ref "UART_USB_CONN") (pin "1") (pinfunction "1_1") (pintype "passive"))
    )
    (net (code "59") (name "unconnected-(UART_USB_CONN-Pad5)") (class "Default")
      (node (ref "UART_USB_CONN") (pin "5") (pinfunction "5_5") (pintype "passive"))
    )
  )
)
